# Controller.net
KiCad netlist of a schematic drawn in Altium Designer
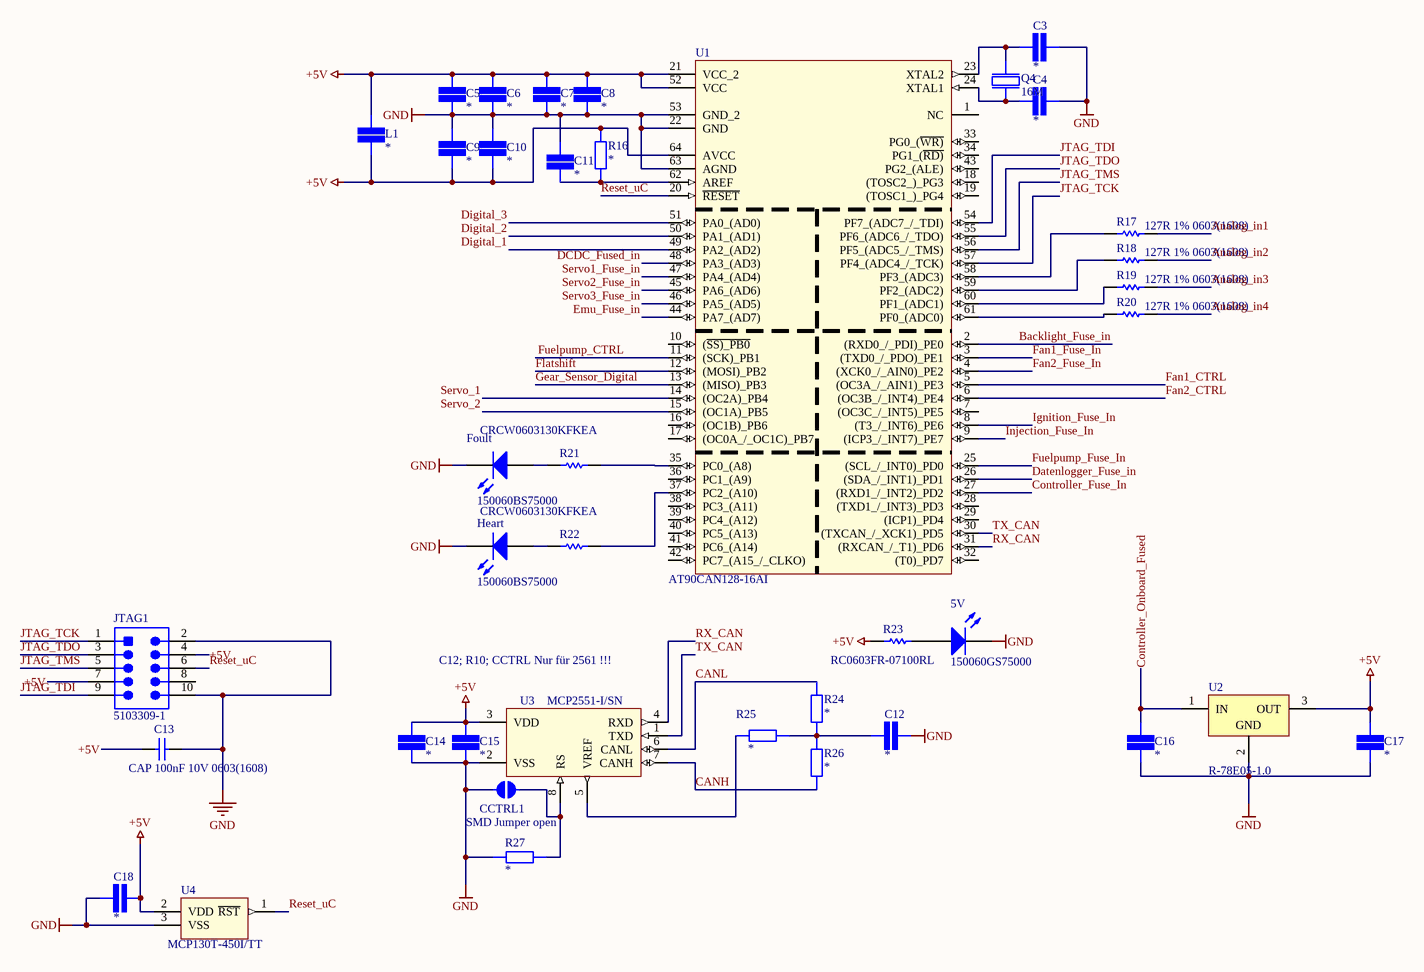
[diagram p0: Controller.SchDoc]

(export (version "E")
  (design (tool "Eeschema 10.0.6"))
  (components
    (comp (ref "5V")
      (value "150060GS75000")
      (footprint "0603_A")
      (description "SMD mono-color Chip LED, WL-SMCW, Green")
      (fields (field (name "MANUFACTURER") "Wuerth Elektronik"))
      (libsource (lib "Altium Content Vault") (part "WE-LED_K1A2-2"))
    )
    (comp (ref "C3")
      (value "SMD Capacitor")
      (footprint "CAP 0603/1608")
      (description "Capacitor with multiple Footprints")
      (fields (field (name "ALTIUM_VALUE") "*"))
      (libsource (lib "") (part "SMD Capacitor_1"))
    )
    (comp (ref "C4")
      (value "SMD Capacitor")
      (footprint "CAP 0603/1608")
      (description "Capacitor with multiple Footprints")
      (fields (field (name "ALTIUM_VALUE") "*"))
      (libsource (lib "") (part "SMD Capacitor_1"))
    )
    (comp (ref "C5")
      (value "SMD Capacitor")
      (footprint "CAP 0603/1608")
      (description "Capacitor with multiple Footprints")
      (fields (field (name "ALTIUM_VALUE") "*"))
      (libsource (lib "Standardbauteile") (part "SMD Capacitor"))
    )
    (comp (ref "C6")
      (value "SMD Capacitor")
      (footprint "CAP 0603/1608")
      (description "Capacitor with multiple Footprints")
      (fields (field (name "ALTIUM_VALUE") "*"))
      (libsource (lib "Standardbauteile") (part "SMD Capacitor"))
    )
    (comp (ref "C7")
      (value "SMD Capacitor")
      (footprint "CAP 0603/1608")
      (description "Capacitor with multiple Footprints")
      (fields (field (name "ALTIUM_VALUE") "*"))
      (libsource (lib "Standardbauteile") (part "SMD Capacitor"))
    )
    (comp (ref "C8")
      (value "SMD Capacitor")
      (footprint "CAP 0603/1608")
      (description "Capacitor with multiple Footprints")
      (fields (field (name "ALTIUM_VALUE") "*"))
      (libsource (lib "Standardbauteile") (part "SMD Capacitor"))
    )
    (comp (ref "C9")
      (value "SMD Capacitor")
      (footprint "CAP 0603/1608")
      (description "Capacitor with multiple Footprints")
      (fields (field (name "ALTIUM_VALUE") "*"))
      (libsource (lib "Standardbauteile") (part "SMD Capacitor"))
    )
    (comp (ref "C10")
      (value "SMD Capacitor")
      (footprint "CAP 0603/1608")
      (description "Capacitor with multiple Footprints")
      (fields (field (name "ALTIUM_VALUE") "*"))
      (libsource (lib "Standardbauteile") (part "SMD Capacitor"))
    )
    (comp (ref "C11")
      (value "SMD Capacitor")
      (footprint "CAP 0603/1608")
      (description "Capacitor with multiple Footprints")
      (fields (field (name "ALTIUM_VALUE") "*"))
      (libsource (lib "Standardbauteile") (part "SMD Capacitor"))
    )
    (comp (ref "C12")
      (value "SMD Capacitor")
      (footprint "CAP 0603/1608")
      (description "Capacitor with multiple Footprints")
      (fields (field (name "ALTIUM_VALUE") "*"))
      (libsource (lib "") (part "SMD Capacitor_2"))
    )
    (comp (ref "C13")
      (value "CAP 100nF 10V 0603(1608)")
      (footprint "CAPC0603(1608)100_L")
      (description "CAP 100nF 10V ±5% 0603 (1608 Metric) Thickness 1mm SMD")
      (fields (field (name "TOLERANCE") "Â±5%"))
      (libsource (lib "Altium Content Vault") (part "CAP"))
    )
    (comp (ref "C14")
      (value "SMD Capacitor")
      (footprint "CAP 0603/1608")
      (description "Capacitor with multiple Footprints")
      (fields (field (name "ALTIUM_VALUE") "*"))
      (libsource (lib "Standardbauteile") (part "SMD Capacitor"))
    )
    (comp (ref "C15")
      (value "SMD Capacitor")
      (footprint "CAP 0603/1608")
      (description "Capacitor with multiple Footprints")
      (fields (field (name "ALTIUM_VALUE") "*"))
      (libsource (lib "Standardbauteile") (part "SMD Capacitor"))
    )
    (comp (ref "C16")
      (value "SMD Capacitor")
      (footprint "CAP 0603/1608")
      (description "Capacitor with multiple Footprints")
      (fields (field (name "ALTIUM_VALUE") "*"))
      (libsource (lib "Standardbauteile") (part "SMD Capacitor"))
    )
    (comp (ref "C17")
      (value "SMD Capacitor")
      (footprint "CAP 0603/1608")
      (description "Capacitor with multiple Footprints")
      (fields (field (name "ALTIUM_VALUE") "*"))
      (libsource (lib "Standardbauteile") (part "SMD Capacitor"))
    )
    (comp (ref "C18")
      (value "SMD Capacitor")
      (footprint "CAP 0603/1608")
      (description "Capacitor with multiple Footprints")
      (fields (field (name "ALTIUM_VALUE") "*"))
      (libsource (lib "") (part "SMD Capacitor_1"))
    )
    (comp (ref "CCTRL1")
      (value "SMD Jumper open")
      (footprint "SMD-JUMPER-OPEN")
      (libsource (lib "Standardbauteile") (part "SMD Jumper open"))
    )
    (comp (ref "Foult")
      (value "150060BS75000")
      (footprint "0603_A")
      (description "SMD mono-color Chip LED, WL-SMCW, Blue")
      (fields (field (name "MANUFACTURER") "Wuerth Elektronik"))
      (libsource (lib "Altium Content Vault") (part "WE-LED_K1A2-2"))
    )
    (comp (ref "Heart")
      (value "150060BS75000")
      (footprint "0603_A")
      (description "SMD mono-color Chip LED, WL-SMCW, Blue")
      (fields (field (name "MANUFACTURER") "Wuerth Elektronik"))
      (libsource (lib "Altium Content Vault") (part "WE-LED_K1A2-2"))
    )
    (comp (ref "JTAG1")
      (value "5103309-1")
      (footprint "TECO-5103309-1_V")
      (fields (field (name "MANUFACTURER") "TE Connectivity"))
      (libsource (lib "Altium Content Vault") (part "CN-2P-M-R10"))
    )
    (comp (ref "L1")
      (value "SMD Capacitor")
      (footprint "CAP 0603/1608")
      (description "Capacitor with multiple Footprints")
      (fields (field (name "ALTIUM_VALUE") "*"))
      (libsource (lib "Standardbauteile") (part "SMD Capacitor"))
    )
    (comp (ref "Q4")
      (value "16M")
      (footprint "NDK NX5032GA")
      (description "16 MHz Quartz")
      (libsource (lib "Standardbauteile") (part "16 MHz Quartz"))
    )
    (comp (ref "R16")
      (value "SMD Resistor")
      (footprint "STACKPOLE CSR0603")
      (description "Resistor with multiple footprints")
      (fields (field (name "ALTIUM_VALUE") "*"))
      (libsource (lib "Standardbauteile") (part "SMD Resistor"))
    )
    (comp (ref "R17")
      (value "127R 1% 0603(1608)")
      (footprint "RESC0603(1608)_N")
      (description "127R 0.1W 1% 0603 (1608 Metric)  SMD")
      (fields (field (name "POWER") "0.1 W") (field (name "TOLERANCE") "1 %"))
      (libsource (lib "Altium Content Vault") (part "RES"))
    )
    (comp (ref "R18")
      (value "127R 1% 0603(1608)")
      (footprint "RESC0603(1608)_N")
      (description "127R 0.1W 1% 0603 (1608 Metric)  SMD")
      (fields (field (name "POWER") "0.1 W") (field (name "TOLERANCE") "1 %"))
      (libsource (lib "Altium Content Vault") (part "RES"))
    )
    (comp (ref "R19")
      (value "127R 1% 0603(1608)")
      (footprint "RESC0603(1608)_N")
      (description "127R 0.1W 1% 0603 (1608 Metric)  SMD")
      (fields (field (name "POWER") "0.1 W") (field (name "TOLERANCE") "1 %"))
      (libsource (lib "Altium Content Vault") (part "RES"))
    )
    (comp (ref "R20")
      (value "127R 1% 0603(1608)")
      (footprint "RESC0603(1608)_N")
      (description "127R 0.1W 1% 0603 (1608 Metric)  SMD")
      (fields (field (name "POWER") "0.1 W") (field (name "TOLERANCE") "1 %"))
      (libsource (lib "Altium Content Vault") (part "RES"))
    )
    (comp (ref "R21")
      (value "CRCW0603130KFKEA")
      (footprint "RESC1609X50X30NL10T20")
      (fields (field (name "MANUFACTURER") "Vishay Dale"))
      (libsource (lib "Altium Content Vault") (part "RES"))
    )
    (comp (ref "R22")
      (value "CRCW0603130KFKEA")
      (footprint "RESC1609X50X30NL10T20")
      (fields (field (name "MANUFACTURER") "Vishay Dale"))
      (libsource (lib "Altium Content Vault") (part "RES"))
    )
    (comp (ref "R23")
      (value "RC0603FR-07100RL")
      (footprint "RESC1608X55X25ML10T15")
      (description "Chip Resistor, 100 Ohm, +/- 1%, 0.1 W, -55 to 155 degC, 0603 (1608 Metric), RoHS, Tape and Reel")
      (fields (field (name "TOLERANCE") "1%") (field (name "MANUFACTURER") "Yageo"))
      (libsource (lib "Altium Content Vault") (part "RES-2"))
    )
    (comp (ref "R24")
      (value "SMD Resistor")
      (footprint "STACKPOLE CSR0603")
      (description "Resistor with multiple footprints")
      (fields (field (name "ALTIUM_VALUE") "*"))
      (libsource (lib "Standardbauteile") (part "SMD Resistor"))
    )
    (comp (ref "R25")
      (value "SMD Resistor")
      (footprint "STACKPOLE CSR0603")
      (description "Resistor with multiple footprints")
      (fields (field (name "ALTIUM_VALUE") "*"))
      (libsource (lib "Standardbauteile") (part "SMD Resistor"))
    )
    (comp (ref "R26")
      (value "SMD Resistor")
      (footprint "STACKPOLE CSR0603")
      (description "Resistor with multiple footprints")
      (fields (field (name "ALTIUM_VALUE") "*"))
      (libsource (lib "Standardbauteile") (part "SMD Resistor"))
    )
    (comp (ref "R27")
      (value "SMD Resistor")
      (footprint "STACKPOLE CSR0603")
      (description "Resistor with multiple footprints")
      (fields (field (name "ALTIUM_VALUE") "*"))
      (libsource (lib "Standardbauteile") (part "SMD Resistor"))
    )
    (comp (ref "U1")
      (value "AT90CAN128-16AI")
      (footprint "*QFP80P1600X1600X120-64N")
      (description "Ic Mcu 8bit 128kb Flash 64tqfp")
      (fields (field (name "MF") "Microchip"))
      (libsource (lib "Eric") (part "AT90CAN128-16AI"))
    )
    (comp (ref "U2")
      (value "R-78E05-1.0")
      (footprint "SIP3_RECOM")
      (description "Nonisolated 5V Switchmode converter")
      (libsource (lib "Standardbauteile") (part "R-78E05-1.0"))
    )
    (comp (ref "U3")
      (value "MCP2551-I/SN")
      (footprint "*SOIC127P600X175-8N")
      (description "MCP2551 Series 5.5 V 1 Mb/s Surface Mount High-Speed CAN Transceiver - SOIC-8")
      (fields (field (name "MF") "Microchip"))
      (libsource (lib "Eric") (part "MCP2551-I/SN"))
    )
    (comp (ref "U4")
      (value "MCP130T-450I/TT")
      (footprint "*SOT95P237X112-3N")
      (description "System Supervisors - Power Supply Monitors with Reset Generators Open Drain Low")
      (fields (field (name "MF") "Microchip") (field (name "MP") "MCP120T-450I/TT"))
      (libsource (lib "Eric") (part "MCP130T-450I/TT"))
    )
  )
  (nets
    (net (code "1") (name "+5V") (class "Default")
      (node (ref "C10") (pin "1") (pinfunction "1_1") (pintype "passive"))
      (node (ref "C13") (pin "1") (pinfunction "1_1") (pintype "passive"))
      (node (ref "C14") (pin "2") (pinfunction "2_2") (pintype "passive"))
      (node (ref "C15") (pin "2") (pinfunction "2_2") (pintype "passive"))
      (node (ref "C17") (pin "2") (pinfunction "2_2") (pintype "passive"))
      (node (ref "C18") (pin "1") (pinfunction "1_1") (pintype "passive"))
      (node (ref "C5") (pin "2") (pinfunction "2_2") (pintype "passive"))
      (node (ref "C6") (pin "2") (pinfunction "2_2") (pintype "passive"))
      (node (ref "C7") (pin "2") (pinfunction "2_2") (pintype "passive"))
      (node (ref "C8") (pin "2") (pinfunction "2_2") (pintype "passive"))
      (node (ref "C9") (pin "1") (pinfunction "1_1") (pintype "passive"))
      (node (ref "JTAG1") (pin "4") (pinfunction "4_4") (pintype "passive"))
      (node (ref "JTAG1") (pin "7") (pinfunction "7_7") (pintype "passive"))
      (node (ref "L1") (pin "1") (pinfunction "1_1") (pintype "passive"))
      (node (ref "L1") (pin "2") (pinfunction "2_2") (pintype "passive"))
      (node (ref "R16") (pin "2") (pinfunction "2_2") (pintype "passive"))
      (node (ref "R23") (pin "1") (pinfunction "1_1") (pintype "passive"))
      (node (ref "U1") (pin "21") (pinfunction "VCC_2_21") (pintype "power_in"))
      (node (ref "U1") (pin "52") (pinfunction "VCC_52") (pintype "power_in"))
      (node (ref "U1") (pin "64") (pinfunction "AVCC_64") (pintype "power_in"))
      (node (ref "U2") (pin "3") (pinfunction "OUT_3") (pintype "power_in"))
      (node (ref "U3") (pin "3") (pinfunction "VDD_3") (pintype "power_in"))
      (node (ref "U4") (pin "2") (pinfunction "VDD_2") (pintype "power_in"))
    )
    (net (code "2") (name "/Analog_in1") (class "Default")
      (node (ref "R17") (pin "1") (pinfunction "1_1") (pintype "passive"))
    )
    (net (code "3") (name "/Analog_in2") (class "Default")
      (node (ref "R18") (pin "1") (pinfunction "1_1") (pintype "passive"))
    )
    (net (code "4") (name "/Analog_in3") (class "Default")
      (node (ref "R19") (pin "1") (pinfunction "1_1") (pintype "passive"))
    )
    (net (code "5") (name "/Analog_in4") (class "Default")
      (node (ref "R20") (pin "1") (pinfunction "1_1") (pintype "passive"))
    )
    (net (code "6") (name "/Backlight_Fuse_in") (class "Default")
      (node (ref "U1") (pin "2") (pinfunction "(RXD0_/_PDI)_PE0_2") (pintype "bidirectional"))
    )
    (net (code "7") (name "/CANH") (class "Default")
      (node (ref "R26") (pin "2") (pinfunction "2_2") (pintype "passive"))
      (node (ref "U3") (pin "7") (pinfunction "CANH_7") (pintype "bidirectional"))
    )
    (net (code "8") (name "/CANL") (class "Default")
      (node (ref "R24") (pin "1") (pinfunction "1_1") (pintype "passive"))
      (node (ref "U3") (pin "6") (pinfunction "CANL_6") (pintype "bidirectional"))
    )
    (net (code "9") (name "/Controller_Fuse_In") (class "Default")
      (node (ref "U1") (pin "27") (pinfunction "(RXD1_/_INT2)_PD2_27") (pintype "bidirectional"))
    )
    (net (code "10") (name "/Controller_Onboard_Fused") (class "Default")
      (node (ref "C16") (pin "2") (pinfunction "2_2") (pintype "passive"))
      (node (ref "U2") (pin "1") (pinfunction "IN_1") (pintype "power_in"))
    )
    (net (code "11") (name "/DCDC_Fused_in") (class "Default")
      (node (ref "U1") (pin "48") (pinfunction "PA3_(AD3)_48") (pintype "bidirectional"))
    )
    (net (code "12") (name "/Datenlogger_Fuse_in") (class "Default")
      (node (ref "U1") (pin "26") (pinfunction "(SDA_/_INT1)_PD1_26") (pintype "bidirectional"))
    )
    (net (code "13") (name "/Digital_1") (class "Default")
      (node (ref "U1") (pin "49") (pinfunction "PA2_(AD2)_49") (pintype "bidirectional"))
    )
    (net (code "14") (name "/Digital_2") (class "Default")
      (node (ref "U1") (pin "50") (pinfunction "PA1_(AD1)_50") (pintype "bidirectional"))
    )
    (net (code "15") (name "/Digital_3") (class "Default")
      (node (ref "U1") (pin "51") (pinfunction "PA0_(AD0)_51") (pintype "bidirectional"))
    )
    (net (code "16") (name "/Emu_Fuse_in") (class "Default")
      (node (ref "U1") (pin "44") (pinfunction "PA7_(AD7)_44") (pintype "bidirectional"))
    )
    (net (code "17") (name "/Fan1_CTRL") (class "Default")
      (node (ref "U1") (pin "5") (pinfunction "(OC3A_/_AIN1)_PE3_5") (pintype "bidirectional"))
    )
    (net (code "18") (name "/Fan1_Fuse_In") (class "Default")
      (node (ref "U1") (pin "3") (pinfunction "(TXD0_/_PDO)_PE1_3") (pintype "bidirectional"))
    )
    (net (code "19") (name "/Fan2_CTRL") (class "Default")
      (node (ref "U1") (pin "6") (pinfunction "(OC3B_/_INT4)_PE4_6") (pintype "bidirectional"))
    )
    (net (code "20") (name "/Fan2_Fuse_In") (class "Default")
      (node (ref "U1") (pin "4") (pinfunction "(XCK0_/_AIN0)_PE2_4") (pintype "bidirectional"))
    )
    (net (code "21") (name "/Flatshift") (class "Default")
      (node (ref "U1") (pin "12") (pinfunction "(MOSI)_PB2_12") (pintype "bidirectional"))
    )
    (net (code "22") (name "/Fuelpump_CTRL") (class "Default")
      (node (ref "U1") (pin "11") (pinfunction "(SCK)_PB1_11") (pintype "bidirectional"))
    )
    (net (code "23") (name "/Fuelpump_Fuse_In") (class "Default")
      (node (ref "U1") (pin "25") (pinfunction "(SCL_/_INT0)_PD0_25") (pintype "bidirectional"))
    )
    (net (code "24") (name "/Gear_Sensor_Digital") (class "Default")
      (node (ref "U1") (pin "13") (pinfunction "(MISO)_PB3_13") (pintype "bidirectional"))
    )
    (net (code "25") (name "/Ignition_Fuse_In") (class "Default")
      (node (ref "U1") (pin "8") (pinfunction "(T3_/_INT6)_PE6_8") (pintype "bidirectional"))
    )
    (net (code "26") (name "/Injection_Fuse_In") (class "Default")
      (node (ref "U1") (pin "9") (pinfunction "(ICP3_/_INT7)_PE7_9") (pintype "bidirectional"))
    )
    (net (code "27") (name "/JTAG_TCK") (class "Default")
      (node (ref "JTAG1") (pin "1") (pinfunction "1_1") (pintype "passive"))
      (node (ref "U1") (pin "57") (pinfunction "PF4_(ADC4_/_TCK)_57") (pintype "bidirectional"))
    )
    (net (code "28") (name "/JTAG_TDI") (class "Default")
      (node (ref "JTAG1") (pin "9") (pinfunction "9_9") (pintype "passive"))
      (node (ref "U1") (pin "54") (pinfunction "PF7_(ADC7_/_TDI)_54") (pintype "bidirectional"))
    )
    (net (code "29") (name "/JTAG_TDO") (class "Default")
      (node (ref "JTAG1") (pin "3") (pinfunction "3_3") (pintype "passive"))
      (node (ref "U1") (pin "55") (pinfunction "PF6_(ADC6_/_TDO)_55") (pintype "bidirectional"))
    )
    (net (code "30") (name "/JTAG_TMS") (class "Default")
      (node (ref "JTAG1") (pin "5") (pinfunction "5_5") (pintype "passive"))
      (node (ref "U1") (pin "56") (pinfunction "PF5_(ADC5_/_TMS)_56") (pintype "bidirectional"))
    )
    (net (code "31") (name "/RX_CAN") (class "Default")
      (node (ref "U1") (pin "31") (pinfunction "(RXCAN_/_T1)_PD6_31") (pintype "bidirectional"))
      (node (ref "U3") (pin "4") (pinfunction "RXD_4") (pintype "output"))
    )
    (net (code "32") (name "/Reset_uC") (class "Default")
      (node (ref "JTAG1") (pin "6") (pinfunction "6_6") (pintype "passive"))
      (node (ref "U1") (pin "20") (pinfunction "~{RESET}_20") (pintype "input"))
      (node (ref "U4") (pin "1") (pinfunction "~{RST}_1") (pintype "output"))
    )
    (net (code "33") (name "/Servo1_Fuse_in") (class "Default")
      (node (ref "U1") (pin "47") (pinfunction "PA4_(AD4)_47") (pintype "bidirectional"))
    )
    (net (code "34") (name "/Servo2_Fuse_in") (class "Default")
      (node (ref "U1") (pin "45") (pinfunction "PA6_(AD6)_45") (pintype "bidirectional"))
    )
    (net (code "35") (name "/Servo3_Fuse_in") (class "Default")
      (node (ref "U1") (pin "46") (pinfunction "PA5_(AD5)_46") (pintype "bidirectional"))
    )
    (net (code "36") (name "/Servo_1") (class "Default")
      (node (ref "U1") (pin "14") (pinfunction "(OC2A)_PB4_14") (pintype "bidirectional"))
    )
    (net (code "37") (name "/Servo_2") (class "Default")
      (node (ref "U1") (pin "15") (pinfunction "(OC1A)_PB5_15") (pintype "bidirectional"))
    )
    (net (code "38") (name "/TX_CAN") (class "Default")
      (node (ref "U1") (pin "30") (pinfunction "(TXCAN_/_XCK1)_PD5_30") (pintype "bidirectional"))
      (node (ref "U3") (pin "1") (pinfunction "TXD_1") (pintype "input"))
    )
    (net (code "39") (name "GND") (class "Default")
      (node (ref "5V") (pin "1") (pinfunction "K_1") (pintype "passive"))
      (node (ref "C10") (pin "2") (pinfunction "2_2") (pintype "passive"))
      (node (ref "C11") (pin "2") (pinfunction "2_2") (pintype "passive"))
      (node (ref "C12") (pin "2") (pinfunction "2_2") (pintype "passive"))
      (node (ref "C13") (pin "2") (pinfunction "2_2") (pintype "passive"))
      (node (ref "C14") (pin "1") (pinfunction "1_1") (pintype "passive"))
      (node (ref "C15") (pin "1") (pinfunction "1_1") (pintype "passive"))
      (node (ref "C16") (pin "1") (pinfunction "1_1") (pintype "passive"))
      (node (ref "C17") (pin "1") (pinfunction "1_1") (pintype "passive"))
      (node (ref "C18") (pin "2") (pinfunction "2_2") (pintype "passive"))
      (node (ref "C3") (pin "1") (pinfunction "1_1") (pintype "passive"))
      (node (ref "C4") (pin "1") (pinfunction "1_1") (pintype "passive"))
      (node (ref "C5") (pin "1") (pinfunction "1_1") (pintype "passive"))
      (node (ref "C6") (pin "1") (pinfunction "1_1") (pintype "passive"))
      (node (ref "C7") (pin "1") (pinfunction "1_1") (pintype "passive"))
      (node (ref "C8") (pin "1") (pinfunction "1_1") (pintype "passive"))
      (node (ref "C9") (pin "2") (pinfunction "2_2") (pintype "passive"))
      (node (ref "CCTRL1") (pin "1") (pinfunction "1_1") (pintype "passive"))
      (node (ref "Foult") (pin "1") (pinfunction "K_1") (pintype "passive"))
      (node (ref "Heart") (pin "1") (pinfunction "K_1") (pintype "passive"))
      (node (ref "JTAG1") (pin "10") (pinfunction "10_10") (pintype "passive"))
      (node (ref "JTAG1") (pin "2") (pinfunction "2_2") (pintype "passive"))
      (node (ref "R27") (pin "1") (pinfunction "1_1") (pintype "passive"))
      (node (ref "U1") (pin "22") (pinfunction "GND_22") (pintype "passive"))
      (node (ref "U1") (pin "53") (pinfunction "GND_2_53") (pintype "passive"))
      (node (ref "U1") (pin "63") (pinfunction "AGND_63") (pintype "passive"))
      (node (ref "U2") (pin "2") (pinfunction "GND_2") (pintype "power_in"))
      (node (ref "U3") (pin "2") (pinfunction "VSS_2") (pintype "passive"))
      (node (ref "U4") (pin "3") (pinfunction "VSS_3") (pintype "power_in"))
    )
    (net (code "40") (name "Net-(5V-A)") (class "Default")
      (node (ref "5V") (pin "2") (pinfunction "A_2") (pintype "passive"))
      (node (ref "R23") (pin "2") (pinfunction "2_2") (pintype "passive"))
    )
    (net (code "41") (name "Net-(C12-Pad1)") (class "Default")
      (node (ref "C12") (pin "1") (pinfunction "1_1") (pintype "passive"))
      (node (ref "R24") (pin "2") (pinfunction "2_2") (pintype "passive"))
      (node (ref "R25") (pin "2") (pinfunction "2_2") (pintype "passive"))
      (node (ref "R26") (pin "1") (pinfunction "1_1") (pintype "passive"))
    )
    (net (code "42") (name "Net-(Foult-A)") (class "Default")
      (node (ref "Foult") (pin "2") (pinfunction "A_2") (pintype "passive"))
      (node (ref "R21") (pin "2") (pinfunction "2_2") (pintype "passive"))
    )
    (net (code "43") (name "Net-(Heart-A)") (class "Default")
      (node (ref "Heart") (pin "2") (pinfunction "A_2") (pintype "passive"))
      (node (ref "R22") (pin "2") (pinfunction "2_2") (pintype "passive"))
    )
    (net (code "44") (name "Net-(U1-AREF)") (class "Default")
      (node (ref "C11") (pin "1") (pinfunction "1_1") (pintype "passive"))
      (node (ref "R16") (pin "1") (pinfunction "1_1") (pintype "passive"))
      (node (ref "U1") (pin "62") (pinfunction "AREF_62") (pintype "input"))
    )
    (net (code "45") (name "Net-(U1-PC0_(A8))") (class "Default")
      (node (ref "R21") (pin "1") (pinfunction "1_1") (pintype "passive"))
      (node (ref "U1") (pin "35") (pinfunction "PC0_(A8)_35") (pintype "bidirectional"))
    )
    (net (code "46") (name "Net-(U1-PC2_(A10))") (class "Default")
      (node (ref "R22") (pin "1") (pinfunction "1_1") (pintype "passive"))
      (node (ref "U1") (pin "37") (pinfunction "PC2_(A10)_37") (pintype "bidirectional"))
    )
    (net (code "47") (name "Net-(U1-PF0_(ADC0))") (class "Default")
      (node (ref "R20") (pin "2") (pinfunction "2_2") (pintype "passive"))
      (node (ref "U1") (pin "61") (pinfunction "PF0_(ADC0)_61") (pintype "bidirectional"))
    )
    (net (code "48") (name "Net-(U1-PF1_(ADC1))") (class "Default")
      (node (ref "R19") (pin "2") (pinfunction "2_2") (pintype "passive"))
      (node (ref "U1") (pin "60") (pinfunction "PF1_(ADC1)_60") (pintype "bidirectional"))
    )
    (net (code "49") (name "Net-(U1-PF2_(ADC2))") (class "Default")
      (node (ref "R18") (pin "2") (pinfunction "2_2") (pintype "passive"))
      (node (ref "U1") (pin "59") (pinfunction "PF2_(ADC2)_59") (pintype "bidirectional"))
    )
    (net (code "50") (name "Net-(U1-PF3_(ADC3))") (class "Default")
      (node (ref "R17") (pin "2") (pinfunction "2_2") (pintype "passive"))
      (node (ref "U1") (pin "58") (pinfunction "PF3_(ADC3)_58") (pintype "bidirectional"))
    )
    (net (code "51") (name "Net-(U1-XTAL1)") (class "Default")
      (node (ref "C4") (pin "2") (pinfunction "2_2") (pintype "passive"))
      (node (ref "Q4") (pin "1") (pinfunction "1_1") (pintype "passive"))
      (node (ref "U1") (pin "24") (pinfunction "XTAL1_24") (pintype "input"))
    )
    (net (code "52") (name "Net-(U1-XTAL2)") (class "Default")
      (node (ref "C3") (pin "2") (pinfunction "2_2") (pintype "passive"))
      (node (ref "Q4") (pin "2") (pinfunction "2_2") (pintype "passive"))
      (node (ref "U1") (pin "23") (pinfunction "XTAL2_23") (pintype "output"))
    )
    (net (code "53") (name "Net-(U3-RS)") (class "Default")
      (node (ref "CCTRL1") (pin "2") (pinfunction "2_2") (pintype "passive"))
      (node (ref "R27") (pin "2") (pinfunction "2_2") (pintype "passive"))
      (node (ref "U3") (pin "8") (pinfunction "RS_8") (pintype "input"))
    )
    (net (code "54") (name "Net-(U3-VREF)") (class "Default")
      (node (ref "R25") (pin "1") (pinfunction "1_1") (pintype "passive"))
      (node (ref "U3") (pin "5") (pinfunction "VREF_5") (pintype "output"))
    )
    (net (code "55") (name "unconnected-(JTAG1-Pad8)") (class "Default")
      (node (ref "JTAG1") (pin "8") (pinfunction "8_8") (pintype "passive"))
    )
    (net (code "56") (name "unconnected-(U1-(ICP1)_PD4-Pad29)") (class "Default")
      (node (ref "U1") (pin "29") (pinfunction "(ICP1)_PD4_29") (pintype "bidirectional"))
    )
    (net (code "57") (name "unconnected-(U1-(OC0A_{slash}_OC1C)_PB7-Pad17)") (class "Default")
      (node (ref "U1") (pin "17") (pinfunction "(OC0A_/_OC1C)_PB7_17") (pintype "bidirectional"))
    )
    (net (code "58") (name "unconnected-(U1-(OC1B)_PB6-Pad16)") (class "Default")
      (node (ref "U1") (pin "16") (pinfunction "(OC1B)_PB6_16") (pintype "bidirectional"))
    )
    (net (code "59") (name "unconnected-(U1-(OC3C_{slash}_INT5)_PE5-Pad7)") (class "Default")
      (node (ref "U1") (pin "7") (pinfunction "(OC3C_/_INT5)_PE5_7") (pintype "bidirectional"))
    )
    (net (code "60") (name "unconnected-(U1-(T0)_PD7-Pad32)") (class "Default")
      (node (ref "U1") (pin "32") (pinfunction "(T0)_PD7_32") (pintype "bidirectional"))
    )
    (net (code "61") (name "unconnected-(U1-(TOSC1_)_PG4-Pad19)") (class "Default")
      (node (ref "U1") (pin "19") (pinfunction "(TOSC1_)_PG4_19") (pintype "bidirectional"))
    )
    (net (code "62") (name "unconnected-(U1-(TOSC2_)_PG3-Pad18)") (class "Default")
      (node (ref "U1") (pin "18") (pinfunction "(TOSC2_)_PG3_18") (pintype "bidirectional"))
    )
    (net (code "63") (name "unconnected-(U1-(TXD1_{slash}_INT3)_PD3-Pad28)") (class "Default")
      (node (ref "U1") (pin "28") (pinfunction "(TXD1_/_INT3)_PD3_28") (pintype "bidirectional"))
    )
    (net (code "64") (name "unconnected-(U1-(~{SS)_PB0}-Pad10)") (class "Default")
      (node (ref "U1") (pin "10") (pinfunction "(~{SS)_PB0}_10") (pintype "bidirectional"))
    )
    (net (code "65") (name "unconnected-(U1-NC-Pad1)") (class "Default")
      (node (ref "U1") (pin "1") (pinfunction "NC_1") (pintype "passive"))
    )
    (net (code "66") (name "unconnected-(U1-PC1_(A9)-Pad36)") (class "Default")
      (node (ref "U1") (pin "36") (pinfunction "PC1_(A9)_36") (pintype "bidirectional"))
    )
    (net (code "67") (name "unconnected-(U1-PC3_(A11)-Pad38)") (class "Default")
      (node (ref "U1") (pin "38") (pinfunction "PC3_(A11)_38") (pintype "bidirectional"))
    )
    (net (code "68") (name "unconnected-(U1-PC4_(A12)-Pad39)") (class "Default")
      (node (ref "U1") (pin "39") (pinfunction "PC4_(A12)_39") (pintype "bidirectional"))
    )
    (net (code "69") (name "unconnected-(U1-PC5_(A13)-Pad40)") (class "Default")
      (node (ref "U1") (pin "40") (pinfunction "PC5_(A13)_40") (pintype "bidirectional"))
    )
    (net (code "70") (name "unconnected-(U1-PC6_(A14)-Pad41)") (class "Default")
      (node (ref "U1") (pin "41") (pinfunction "PC6_(A14)_41") (pintype "bidirectional"))
    )
    (net (code "71") (name "unconnected-(U1-PC7_(A15_{slash}_CLKO)-Pad42)") (class "Default")
      (node (ref "U1") (pin "42") (pinfunction "PC7_(A15_/_CLKO)_42") (pintype "bidirectional"))
    )
    (net (code "72") (name "unconnected-(U1-PG0_(~{WR)}-Pad33)") (class "Default")
      (node (ref "U1") (pin "33") (pinfunction "PG0_(~{WR)}_33") (pintype "bidirectional"))
    )
    (net (code "73") (name "unconnected-(U1-PG1_(~{RD)}-Pad34)") (class "Default")
      (node (ref "U1") (pin "34") (pinfunction "PG1_(~{RD)}_34") (pintype "bidirectional"))
    )
    (net (code "74") (name "unconnected-(U1-PG2_(ALE)-Pad43)") (class "Default")
      (node (ref "U1") (pin "43") (pinfunction "PG2_(ALE)_43") (pintype "bidirectional"))
    )
  )
)
